# Power_Supply_Unit.net
KiCad netlist of a schematic drawn in Altium Designer
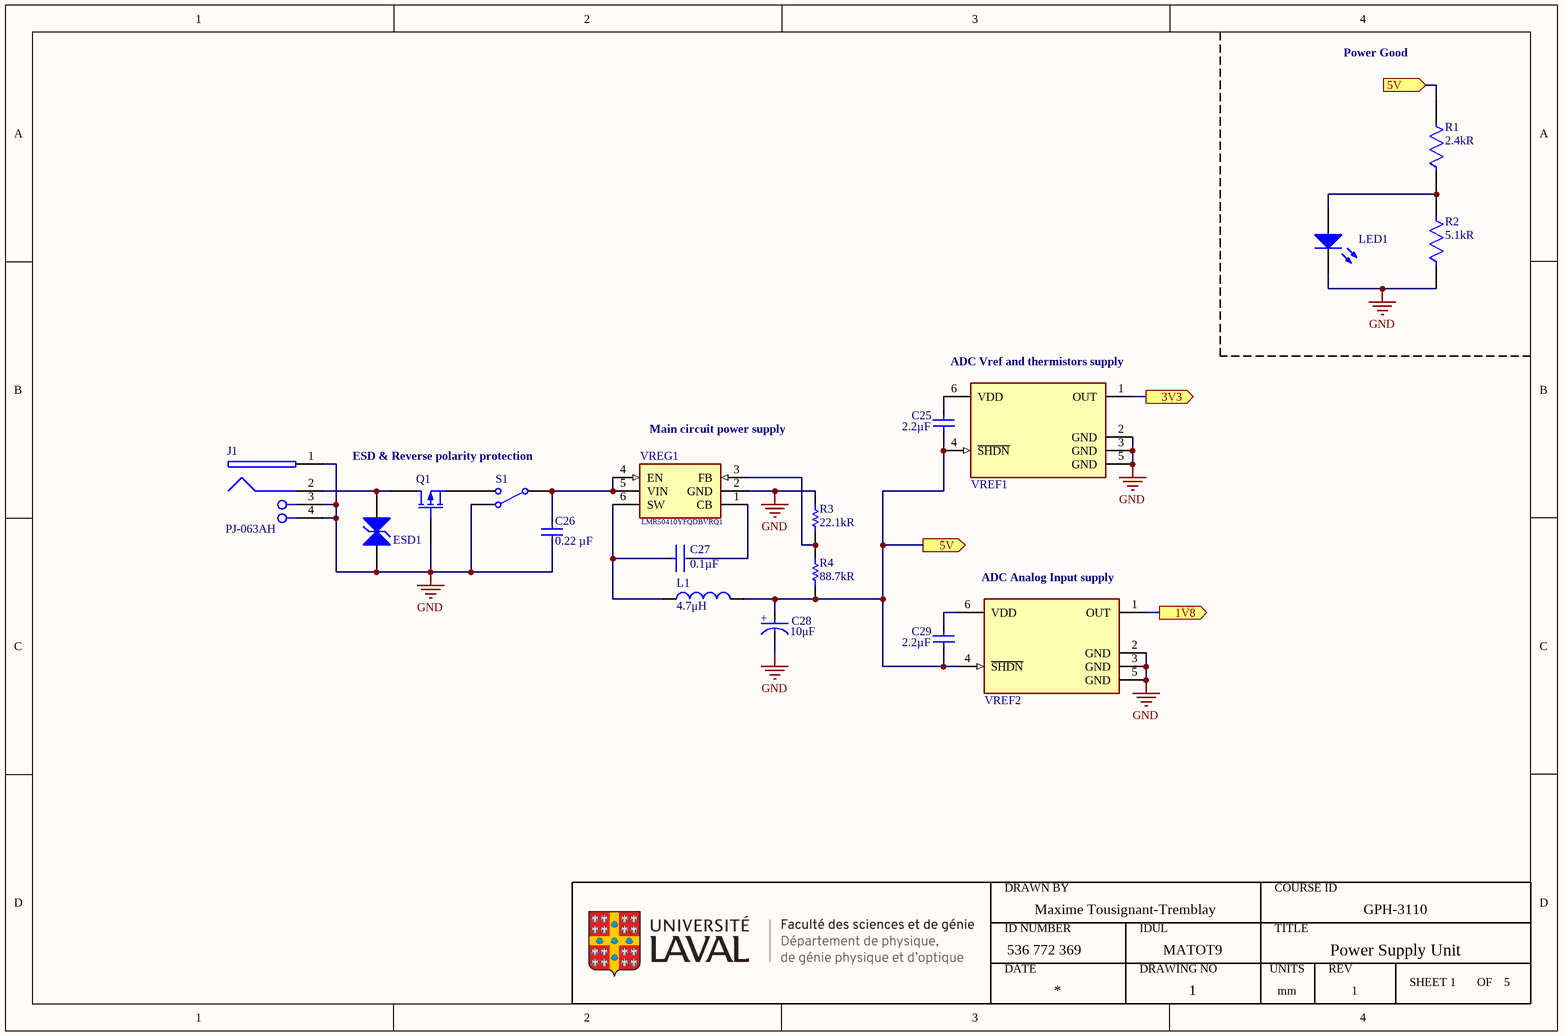
[diagram p0: Power Supply Unit.SchDoc]

(export (version "E")
  (design (tool "Eeschema 10.0.6"))
  (components
    (comp (ref "*2")
      (value "ULaval FSG-DPGPO")
      (libsource (lib "ULaval Title Block") (part "ULaval FSG-DPGPO"))
    )
    (comp (ref "C25")
      (value "CC0603KRX7R5BB225")
      (footprint "CC0603KRX7R5BB225")
      (description "2.2 µF ±10% 6.3V Ceramic Capacitor X7R 0603 (1608 Metric)")
      (fields
        (field (name "CAPACITANCE") "2.2µF")
        (field (name "MANUFACTURER") "Yageo")
        (field (name "TOLERANCE") "±10%")
      )
      (libsource (lib "Arduino Nano Every Symbols") (part "CC0603KRX7R5BB225"))
    )
    (comp (ref "C26")
      (value "0.22 µF")
      (footprint "GRM188R71E224KA88D")
      (description "0.22 µF ±10% 25V Ceramic Capacitor X7R 0603 (1608 Metric)")
      (fields
        (field (name "PART NUMBER") "GRM188R71E224KA88D")
        (field (name "MANUFACTURER") "Murata Electronics")
      )
      (libsource (lib "Arduino Nano Every Symbols") (part "GRM188R71E224KA88D"))
    )
    (comp (ref "C27")
      (value "~")
      (footprint "CAP 0603_1608")
      (description "0.1 µF ±5% 50V Ceramic Capacitor X7R 0603 (1608 Metric)")
      (fields
        (field (name "PART NUMBER") "CC0603JRX7R9BB104")
        (field (name "CAPACITANCE") "0.1µF")
        (field (name "MANUFACTURER") "Yageo")
      )
      (libsource (lib "Arduino Nano Every Symbols") (part "CC0603JRX7R9BB104"))
    )
    (comp (ref "C28")
      (value "10μF")
      (footprint "293D106X9016B2TE3")
      (description "10 µF Molded Tantalum Capacitors 16 V 1411 (3528 Metric) 2Ohm")
      (fields (field (name "Comment") "293D106X9016B2TE3"))
      (libsource (lib "Arduino Nano Every Symbols") (part "293D106X9016B2TE3"))
    )
    (comp (ref "C29")
      (value "CC0603KRX7R5BB225")
      (footprint "CC0603KRX7R5BB225")
      (description "2.2 µF ±10% 6.3V Ceramic Capacitor X7R 0603 (1608 Metric)")
      (fields
        (field (name "CAPACITANCE") "2.2µF")
        (field (name "MANUFACTURER") "Yageo")
        (field (name "TOLERANCE") "±10%")
      )
      (libsource (lib "Arduino Nano Every Symbols") (part "CC0603KRX7R5BB225"))
    )
    (comp (ref "ESD1")
      (value "SMBJ20CA")
      (footprint "SMBJ20CA")
      (description "32.4V Clamp 18.6A Ipp Tvs Diode Surface Mount SMB (DO-214AA)")
      (libsource (lib "Arduino Nano Every Symbols") (part "SMBJ20CA"))
    )
    (comp (ref "J1")
      (value "PJ-063AH")
      (footprint "PJ-063AH")
      (description "Power Barrel Connector Jack 2.10mm ID (0.083\"), 5.50mm OD (0.217\") Through Hole, Right Angle")
      (libsource (lib "Arduino Nano Every Symbols") (part "PJ-063AH"))
    )
    (comp (ref "L1")
      (value "4.7μH")
      (footprint "ILSB1206ER4R7K")
      (description "4.7 µH Shielded Multilayer Inductor 50 mA 900mOhm Max 1206 (3216 Metric)")
      (fields (field (name "TOLERANCE") "10%") (field (name "Comment") "ILSB1206ER4R7K"))
      (libsource (lib "Arduino Nano Every Symbols") (part "ILSB1206ER4R7K"))
    )
    (comp (ref "LED1")
      (value "151053GS03000")
      (footprint "Type 5mm")
      (description "Led, Green, T-1 3/4 (5Mm), 522 Nm, 3.4 V, 30 Ma, 10 Cd Rohs Compliant: Yes")
      (libsource (lib "Laval University") (part "WE-LED_K1A2-2"))
    )
    (comp (ref "Q1")
      (value "IRLML9303TRPBF")
      (footprint "IRLML9303TRPBF")
      (description "P-Channel 30 V 2.3A (Ta) 1.25W (Ta) Surface Mount Micro3™/SOT-23")
      (fields (field (name "MANUFACTURER") "Infineon Technologies"))
      (libsource (lib "Arduino Nano Every Symbols") (part "IRLML9303TRPBF"))
    )
    (comp (ref "R1")
      (value "2.4kR")
      (footprint "FP-AC0603-IPC_C")
      (description "Res Thick Film 0603 2.4K Ohm 1% 0.1W(1/10W) ±100ppm/C Pad SMD Automotive T/R")
      (fields (field (name "TOLERANCE") "1%") (field (name "Comment") "AC0603FR-072K4L"))
      (libsource (lib "Laval University") (part "1029c3af85768c4190bb7ad29bc67b5"))
    )
    (comp (ref "R2")
      (value "5.1kR")
      (footprint "FP-AC0603-IPC_C")
      (description "Res Thick Film 0603 5.1K Ohm 1% 1/10W ±100ppm/°C Molded SMD Paper T/R")
      (fields (field (name "TOLERANCE") "1%") (field (name "Comment") "AC0603FR-075K1L"))
      (libsource (lib "Laval University") (part "1029c3af85768c4190bb7ad29bc67b5"))
    )
    (comp (ref "R3")
      (value "22.1kR")
      (footprint "CRCW060322K1FKEA-Footprint-2")
      (description "Res Thick Film 0603 22.1K Ohm 1% 1/10W ±100ppm/°C Molded SMD SMD Paper T/R")
      (fields (field (name "TOLERANCE") "1%") (field (name "Comment") "CRCW060322K1FKEA"))
      (libsource (lib "Laval University") (part "RES"))
    )
    (comp (ref "R4")
      (value "88.7kR")
      (footprint "FP-CRCW0603-e3-IPC_B")
      (description "D11/CRCW0603 100 88K7 1% ET5 e3")
      (fields (field (name "TOLERANCE") "1%") (field (name "Comment") "CRCW060388K7FKEB"))
      (libsource (lib "") (part "1029c3af85768c4190bb7ad29bc67b5_1"))
    )
    (comp (ref "S1")
      (value "Single-Pole, Double-Throw Switch")
      (libsource (lib "Simulation Generic Components") (part "SPDT SW"))
    )
    (comp (ref "VREF1")
      (value "MCP1501T-33E/CHY")
      (footprint "MCP1501T-33E/CHY")
      (description "Series Voltage Reference IC Fixed 3.3V V ±0.1% 20 mA SOT-23-6")
      (fields (field (name "TOLERANCE") "0.08%"))
      (libsource (lib "Arduino Nano Every Symbols") (part "MCP1501T-33E/CHY"))
    )
    (comp (ref "VREF2")
      (value "MCP1501T-18E/CHY")
      (footprint "MCP1501T-18E/CHY")
      (description "Series Voltage Reference IC Fixed 31.8V V ±0.1% 20 mA SOT-23-6")
      (fields (field (name "TOLERANCE") "0.08%"))
      (libsource (lib "Arduino Nano Every Symbols") (part "MCP1501T-18E/CHY"))
    )
    (comp (ref "VREG1")
      (value "LMR50410YFQDBVRQ1")
      (footprint "LMR50410YFQDBVRQ1")
      (description "Buck Switching Regulator IC Positive Adjustable 1V 1 Output 1A SOT-23-6")
      (fields (field (name "MOUSER PART NUMBER") "595-MR50410YFQDBVRQ1"))
      (libsource (lib "Arduino Nano Every Symbols") (part "LMR50410YFQDBVRQ1"))
    )
  )
  (nets
    (net (code "1") (name "/1V8") (class "Default")
      (node (ref "VREF2") (pin "1") (pinfunction "OUT_1") (pintype "power_in"))
    )
    (net (code "2") (name "/3V3") (class "Default")
      (node (ref "VREF1") (pin "1") (pinfunction "OUT_1") (pintype "power_in"))
    )
    (net (code "3") (name "/5V") (class "Default")
      (node (ref "C25") (pin "2") (pinfunction "2_2") (pintype "passive"))
      (node (ref "C28") (pin "2") (pinfunction "A_2") (pintype "passive"))
      (node (ref "C29") (pin "2") (pinfunction "2_2") (pintype "passive"))
      (node (ref "L1") (pin "2") (pinfunction "2_2") (pintype "passive"))
      (node (ref "R1") (pin "2") (pinfunction "2_2") (pintype "passive"))
      (node (ref "R4") (pin "1") (pinfunction "1_1") (pintype "passive"))
      (node (ref "VREF1") (pin "4") (pinfunction "~{SHDN}_4") (pintype "input"))
      (node (ref "VREF2") (pin "4") (pinfunction "~{SHDN}_4") (pintype "input"))
    )
    (net (code "4") (name "GND") (class "Default")
      (node (ref "C26") (pin "1") (pinfunction "1_1") (pintype "passive"))
      (node (ref "C28") (pin "1") (pinfunction "C_1") (pintype "passive"))
      (node (ref "ESD1") (pin "2") (pinfunction "2_2") (pintype "passive"))
      (node (ref "J1") (pin "1") (pinfunction "1_1") (pintype "passive"))
      (node (ref "J1") (pin "3") (pinfunction "SHLD_3") (pintype "passive"))
      (node (ref "J1") (pin "4") (pinfunction "SHLD_4") (pintype "passive"))
      (node (ref "LED1") (pin "1") (pinfunction "K_1") (pintype "passive"))
      (node (ref "Q1") (pin "2") (pinfunction "G_2") (pintype "passive"))
      (node (ref "R2") (pin "1") (pinfunction "1_1") (pintype "passive"))
      (node (ref "R3") (pin "2") (pinfunction "2_2") (pintype "passive"))
      (node (ref "S1") (pin "3") (pinfunction "3_3") (pintype "passive"))
      (node (ref "VREF1") (pin "2") (pinfunction "GND_2") (pintype "power_in"))
      (node (ref "VREF1") (pin "3") (pinfunction "GND_3") (pintype "power_in"))
      (node (ref "VREF1") (pin "5") (pinfunction "GND_5") (pintype "power_in"))
      (node (ref "VREF2") (pin "2") (pinfunction "GND_2") (pintype "power_in"))
      (node (ref "VREF2") (pin "3") (pinfunction "GND_3") (pintype "power_in"))
      (node (ref "VREF2") (pin "5") (pinfunction "GND_5") (pintype "power_in"))
      (node (ref "VREG1") (pin "2") (pinfunction "GND_2") (pintype "power_in"))
    )
    (net (code "5") (name "Net-(LED1-A)") (class "Default")
      (node (ref "LED1") (pin "2") (pinfunction "A_2") (pintype "passive"))
      (node (ref "R1") (pin "1") (pinfunction "1_1") (pintype "passive"))
      (node (ref "R2") (pin "2") (pinfunction "2_2") (pintype "passive"))
    )
    (net (code "6") (name "Net-(Q1-D)") (class "Default")
      (node (ref "ESD1") (pin "1") (pinfunction "1_1") (pintype "passive"))
      (node (ref "J1") (pin "2") (pinfunction "2_2") (pintype "passive"))
      (node (ref "Q1") (pin "1") (pinfunction "D_1") (pintype "passive"))
    )
    (net (code "7") (name "Net-(Q1-S)") (class "Default")
      (node (ref "Q1") (pin "3") (pinfunction "S_3") (pintype "passive"))
      (node (ref "S1") (pin "2") (pinfunction "2_2") (pintype "passive"))
    )
    (net (code "8") (name "Net-(VREF1-VDD)") (class "Default")
      (node (ref "C25") (pin "1") (pinfunction "1_1") (pintype "passive"))
      (node (ref "VREF1") (pin "6") (pinfunction "VDD_6") (pintype "power_in"))
    )
    (net (code "9") (name "Net-(VREF2-VDD)") (class "Default")
      (node (ref "C29") (pin "1") (pinfunction "1_1") (pintype "passive"))
      (node (ref "VREF2") (pin "6") (pinfunction "VDD_6") (pintype "power_in"))
    )
    (net (code "10") (name "Net-(VREG1-CB)") (class "Default")
      (node (ref "C27") (pin "2") (pinfunction "2_2") (pintype "passive"))
      (node (ref "VREG1") (pin "1") (pinfunction "CB_1") (pintype "power_in"))
    )
    (net (code "11") (name "Net-(VREG1-EN)") (class "Default")
      (node (ref "C26") (pin "2") (pinfunction "2_2") (pintype "passive"))
      (node (ref "S1") (pin "1") (pinfunction "1_1") (pintype "passive"))
      (node (ref "VREG1") (pin "4") (pinfunction "EN_4") (pintype "input"))
      (node (ref "VREG1") (pin "5") (pinfunction "VIN_5") (pintype "power_in"))
    )
    (net (code "12") (name "Net-(VREG1-FB)") (class "Default")
      (node (ref "R3") (pin "1") (pinfunction "1_1") (pintype "passive"))
      (node (ref "R4") (pin "2") (pinfunction "2_2") (pintype "passive"))
      (node (ref "VREG1") (pin "3") (pinfunction "FB_3") (pintype "input"))
    )
    (net (code "13") (name "Net-(VREG1-SW)") (class "Default")
      (node (ref "C27") (pin "1") (pinfunction "1_1") (pintype "passive"))
      (node (ref "L1") (pin "1") (pinfunction "1_1") (pintype "passive"))
      (node (ref "VREG1") (pin "6") (pinfunction "SW_6") (pintype "power_in"))
    )
  )
)
